# COUNT-1-BCD.net
KiCad netlist of a schematic drawn in EAGLE
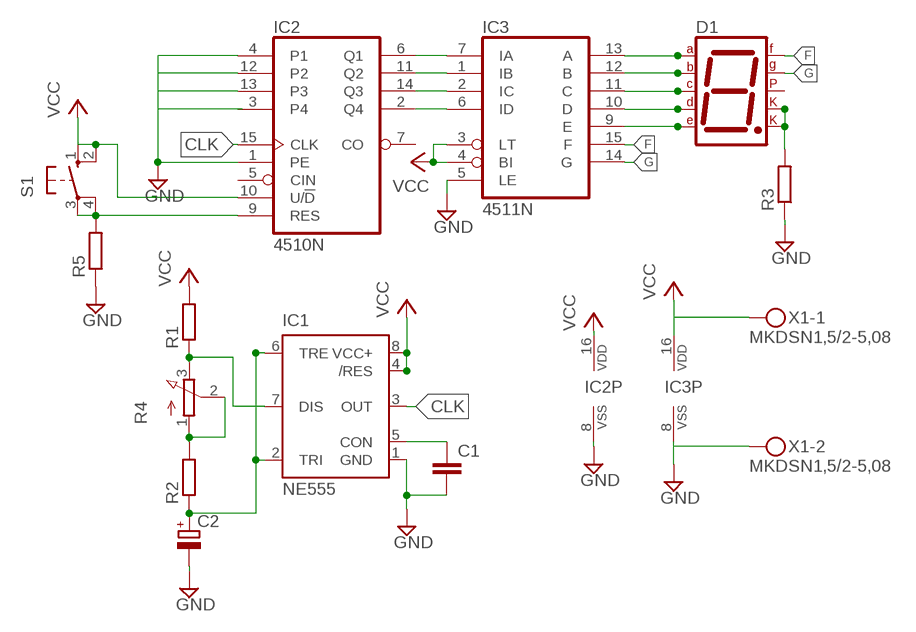
[diagram p0: schematic, sheet 1]

(export (version "E")
  (design (tool "Eeschema 10.0.6"))
  (components
    (comp (ref "C1")
      (value "C2.5/2")
      (footprint "eagle-import:C2.5-2")
      (libsource (lib "eagle-import") (part "C2.5/2"))
    )
    (comp (ref "C2")
      (value "CPOL-EUE2,5-6E")
      (footprint "eagle-import:E2,5-6E")
      (libsource (lib "eagle-import") (part "CPOL-EUE2,5-6E"))
    )
    (comp (ref "D1")
      (value "7SEG-CK")
      (footprint "eagle-import:7SEG-13")
      (libsource (lib "eagle-import") (part "7SEG-CK"))
    )
    (comp (ref "IC1")
      (value "NE555")
      (footprint "eagle-import:DIL-08")
      (fields (field (name "MF") "Arrow Electronics") (field (name "MPN") "NE555N"))
      (libsource (lib "eagle-import") (part "NE555"))
    )
    (comp (ref "IC2")
      (value "4510N")
      (footprint "eagle-import:DIL16")
      (libsource (lib "eagle-import") (part "4510N"))
    )
    (comp (ref "IC3")
      (value "4511N")
      (footprint "eagle-import:DIL16")
      (libsource (lib "eagle-import") (part "4511N"))
    )
    (comp (ref "R1")
      (value "R-EU_0204/7")
      (footprint "eagle-import:0204_7")
      (libsource (lib "eagle-import") (part "R-EU_0204/7"))
    )
    (comp (ref "R2")
      (value "R-EU_0204/7")
      (footprint "eagle-import:0204_7")
      (libsource (lib "eagle-import") (part "R-EU_0204/7"))
    )
    (comp (ref "R3")
      (value "R-EU_0204/7")
      (footprint "eagle-import:0204_7")
      (libsource (lib "eagle-import") (part "R-EU_0204/7"))
    )
    (comp (ref "R4")
      (value "3RP/1610N")
      (footprint "eagle-import:3RP_1610N")
      (libsource (lib "eagle-import") (part "3RP/1610N"))
    )
    (comp (ref "R5")
      (value "R-EU_0204/7")
      (footprint "eagle-import:0204_7")
      (libsource (lib "eagle-import") (part "R-EU_0204/7"))
    )
    (comp (ref "S1")
      (value "10-XX")
      (footprint "eagle-import:B3F-10XX")
      (fields (field (name "MPN") "B3F-1000"))
      (libsource (lib "eagle-import") (part "10-XX"))
    )
    (comp (ref "X1")
      (value "MKDSN1,5/2-5,08")
      (footprint "eagle-import:MKDSN1,5_2-5,08")
      (libsource (lib "eagle-import") (part "MKDSN1,5/2-5,08"))
    )
  )
  (nets
    (net (code "1") (name "CLK") (class "Default")
      (node (ref "IC1") (pin "3") (pinfunction "OUT_3") (pintype "output"))
      (node (ref "IC2") (pin "15") (pinfunction "CLK_15") (pintype "input"))
    )
    (net (code "2") (name "F") (class "Default")
      (node (ref "D1") (pin "9") (pinfunction "F_9") (pintype "passive"))
      (node (ref "IC3") (pin "15") (pinfunction "F_15") (pintype "output"))
    )
    (net (code "3") (name "G") (class "Default")
      (node (ref "D1") (pin "10") (pinfunction "G_10") (pintype "passive"))
      (node (ref "IC3") (pin "14") (pinfunction "G_14") (pintype "output"))
    )
    (net (code "4") (name "GND") (class "Default")
      (node (ref "C1") (pin "2") (pinfunction "2_2") (pintype "passive"))
      (node (ref "C2") (pin "-") (pinfunction "-_-") (pintype "passive"))
      (node (ref "IC1") (pin "1") (pinfunction "GND_1") (pintype "power_in"))
      (node (ref "IC2") (pin "1") (pinfunction "PE_1") (pintype "input"))
      (node (ref "IC2") (pin "12") (pinfunction "P2_12") (pintype "input"))
      (node (ref "IC2") (pin "13") (pinfunction "P3_13") (pintype "input"))
      (node (ref "IC2") (pin "4") (pinfunction "P1_4") (pintype "input"))
      (node (ref "IC2") (pin "8") (pinfunction "VSS_8") (pintype "power_in"))
      (node (ref "IC3") (pin "5") (pinfunction "LE_5") (pintype "input"))
      (node (ref "IC3") (pin "8") (pinfunction "VSS_8") (pintype "power_in"))
      (node (ref "R3") (pin "1") (pinfunction "1_1") (pintype "passive"))
      (node (ref "R5") (pin "1") (pinfunction "1_1") (pintype "passive"))
      (node (ref "X1") (pin "2") (pinfunction "KL_2") (pintype "passive"))
    )
    (net (code "5") (name "Net-(D1-A)") (class "Default")
      (node (ref "D1") (pin "7") (pinfunction "A_7") (pintype "passive"))
      (node (ref "IC3") (pin "13") (pinfunction "A_13") (pintype "output"))
    )
    (net (code "6") (name "Net-(D1-B)") (class "Default")
      (node (ref "D1") (pin "6") (pinfunction "B_6") (pintype "passive"))
      (node (ref "IC3") (pin "12") (pinfunction "B_12") (pintype "output"))
    )
    (net (code "7") (name "Net-(D1-C)") (class "Default")
      (node (ref "D1") (pin "4") (pinfunction "C_4") (pintype "passive"))
      (node (ref "IC3") (pin "11") (pinfunction "C_11") (pintype "output"))
    )
    (net (code "8") (name "Net-(D1-CK1)") (class "Default")
      (node (ref "D1") (pin "3") (pinfunction "CK1_3") (pintype "passive"))
      (node (ref "D1") (pin "8") (pinfunction "CK2_8") (pintype "passive"))
      (node (ref "R3") (pin "2") (pinfunction "2_2") (pintype "passive"))
    )
    (net (code "9") (name "Net-(D1-D)") (class "Default")
      (node (ref "D1") (pin "2") (pinfunction "D_2") (pintype "passive"))
      (node (ref "IC3") (pin "10") (pinfunction "D_10") (pintype "output"))
    )
    (net (code "10") (name "Net-(D1-E)") (class "Default")
      (node (ref "D1") (pin "1") (pinfunction "E_1") (pintype "passive"))
      (node (ref "IC3") (pin "9") (pinfunction "E_9") (pintype "output"))
    )
    (net (code "11") (name "Net-(IC1-CON)") (class "Default")
      (node (ref "C1") (pin "1") (pinfunction "1_1") (pintype "passive"))
      (node (ref "IC1") (pin "5") (pinfunction "CON_5") (pintype "input"))
    )
    (net (code "12") (name "Net-(IC1-DIS)") (class "Default")
      (node (ref "IC1") (pin "7") (pinfunction "DIS_7") (pintype "input"))
      (node (ref "R1") (pin "1") (pinfunction "1_1") (pintype "passive"))
      (node (ref "R4") (pin "3") (pinfunction "E_3") (pintype "passive"))
    )
    (net (code "13") (name "Net-(IC1-TRE)") (class "Default")
      (node (ref "C2") (pin "+") (pinfunction "+_+") (pintype "passive"))
      (node (ref "IC1") (pin "2") (pinfunction "TRI_2") (pintype "input"))
      (node (ref "IC1") (pin "6") (pinfunction "TRE_6") (pintype "input"))
      (node (ref "R2") (pin "1") (pinfunction "1_1") (pintype "passive"))
    )
    (net (code "14") (name "Net-(IC2A-Q1)") (class "Default")
      (node (ref "IC2") (pin "6") (pinfunction "Q1_6") (pintype "output"))
      (node (ref "IC3") (pin "7") (pinfunction "IA_7") (pintype "input"))
    )
    (net (code "15") (name "Net-(IC2A-Q2)") (class "Default")
      (node (ref "IC2") (pin "11") (pinfunction "Q2_11") (pintype "output"))
      (node (ref "IC3") (pin "1") (pinfunction "IB_1") (pintype "input"))
    )
    (net (code "16") (name "Net-(IC2A-Q3)") (class "Default")
      (node (ref "IC2") (pin "14") (pinfunction "Q3_14") (pintype "output"))
      (node (ref "IC3") (pin "2") (pinfunction "IC_2") (pintype "input"))
    )
    (net (code "17") (name "Net-(IC2A-Q4)") (class "Default")
      (node (ref "IC2") (pin "2") (pinfunction "Q4_2") (pintype "output"))
      (node (ref "IC3") (pin "6") (pinfunction "ID_6") (pintype "input"))
    )
    (net (code "18") (name "Net-(IC2A-RES)") (class "Default")
      (node (ref "IC2") (pin "9") (pinfunction "RES_9") (pintype "input"))
      (node (ref "R5") (pin "2") (pinfunction "2_2") (pintype "passive"))
      (node (ref "S1") (pin "3") (pinfunction "P_3") (pintype "passive"))
      (node (ref "S1") (pin "4") (pinfunction "P1_4") (pintype "passive"))
    )
    (net (code "19") (name "Net-(R4-A)") (class "Default")
      (node (ref "R2") (pin "2") (pinfunction "2_2") (pintype "passive"))
      (node (ref "R4") (pin "1") (pinfunction "A_1") (pintype "passive"))
      (node (ref "R4") (pin "2") (pinfunction "S_2") (pintype "passive"))
    )
    (net (code "20") (name "VCC") (class "Default")
      (node (ref "IC1") (pin "4") (pinfunction "/RES_4") (pintype "input"))
      (node (ref "IC1") (pin "8") (pinfunction "VCC+_8") (pintype "power_in"))
      (node (ref "IC2") (pin "10") (pinfunction "U/~{D}_10") (pintype "input"))
      (node (ref "IC2") (pin "16") (pinfunction "VDD_16") (pintype "power_in"))
      (node (ref "IC3") (pin "16") (pinfunction "VDD_16") (pintype "power_in"))
      (node (ref "IC3") (pin "3") (pinfunction "LT_3") (pintype "input"))
      (node (ref "IC3") (pin "4") (pinfunction "BI_4") (pintype "input"))
      (node (ref "R1") (pin "2") (pinfunction "2_2") (pintype "passive"))
      (node (ref "S1") (pin "1") (pinfunction "S_1") (pintype "passive"))
      (node (ref "S1") (pin "2") (pinfunction "S1_2") (pintype "passive"))
      (node (ref "X1") (pin "1") (pinfunction "KL_1") (pintype "passive"))
    )
    (net (code "21") (name "unconnected-(D1-DP-Pad5)") (class "Default")
      (node (ref "D1") (pin "5") (pinfunction "DP_5") (pintype "passive"))
    )
    (net (code "22") (name "unconnected-(IC2A-CIN-Pad5)") (class "Default")
      (node (ref "IC2") (pin "5") (pinfunction "CIN_5") (pintype "input"))
    )
    (net (code "23") (name "unconnected-(IC2A-CO-Pad7)") (class "Default")
      (node (ref "IC2") (pin "7") (pinfunction "CO_7") (pintype "output"))
    )
    (net (code "24") (name "unconnected-(IC2A-P4-Pad3)") (class "Default")
      (node (ref "IC2") (pin "3") (pinfunction "P4_3") (pintype "input"))
    )
  )
)
